# 6Ch_24Bit_FB_FeatherWing_RevB.net
KiCad netlist of a schematic drawn in EAGLE
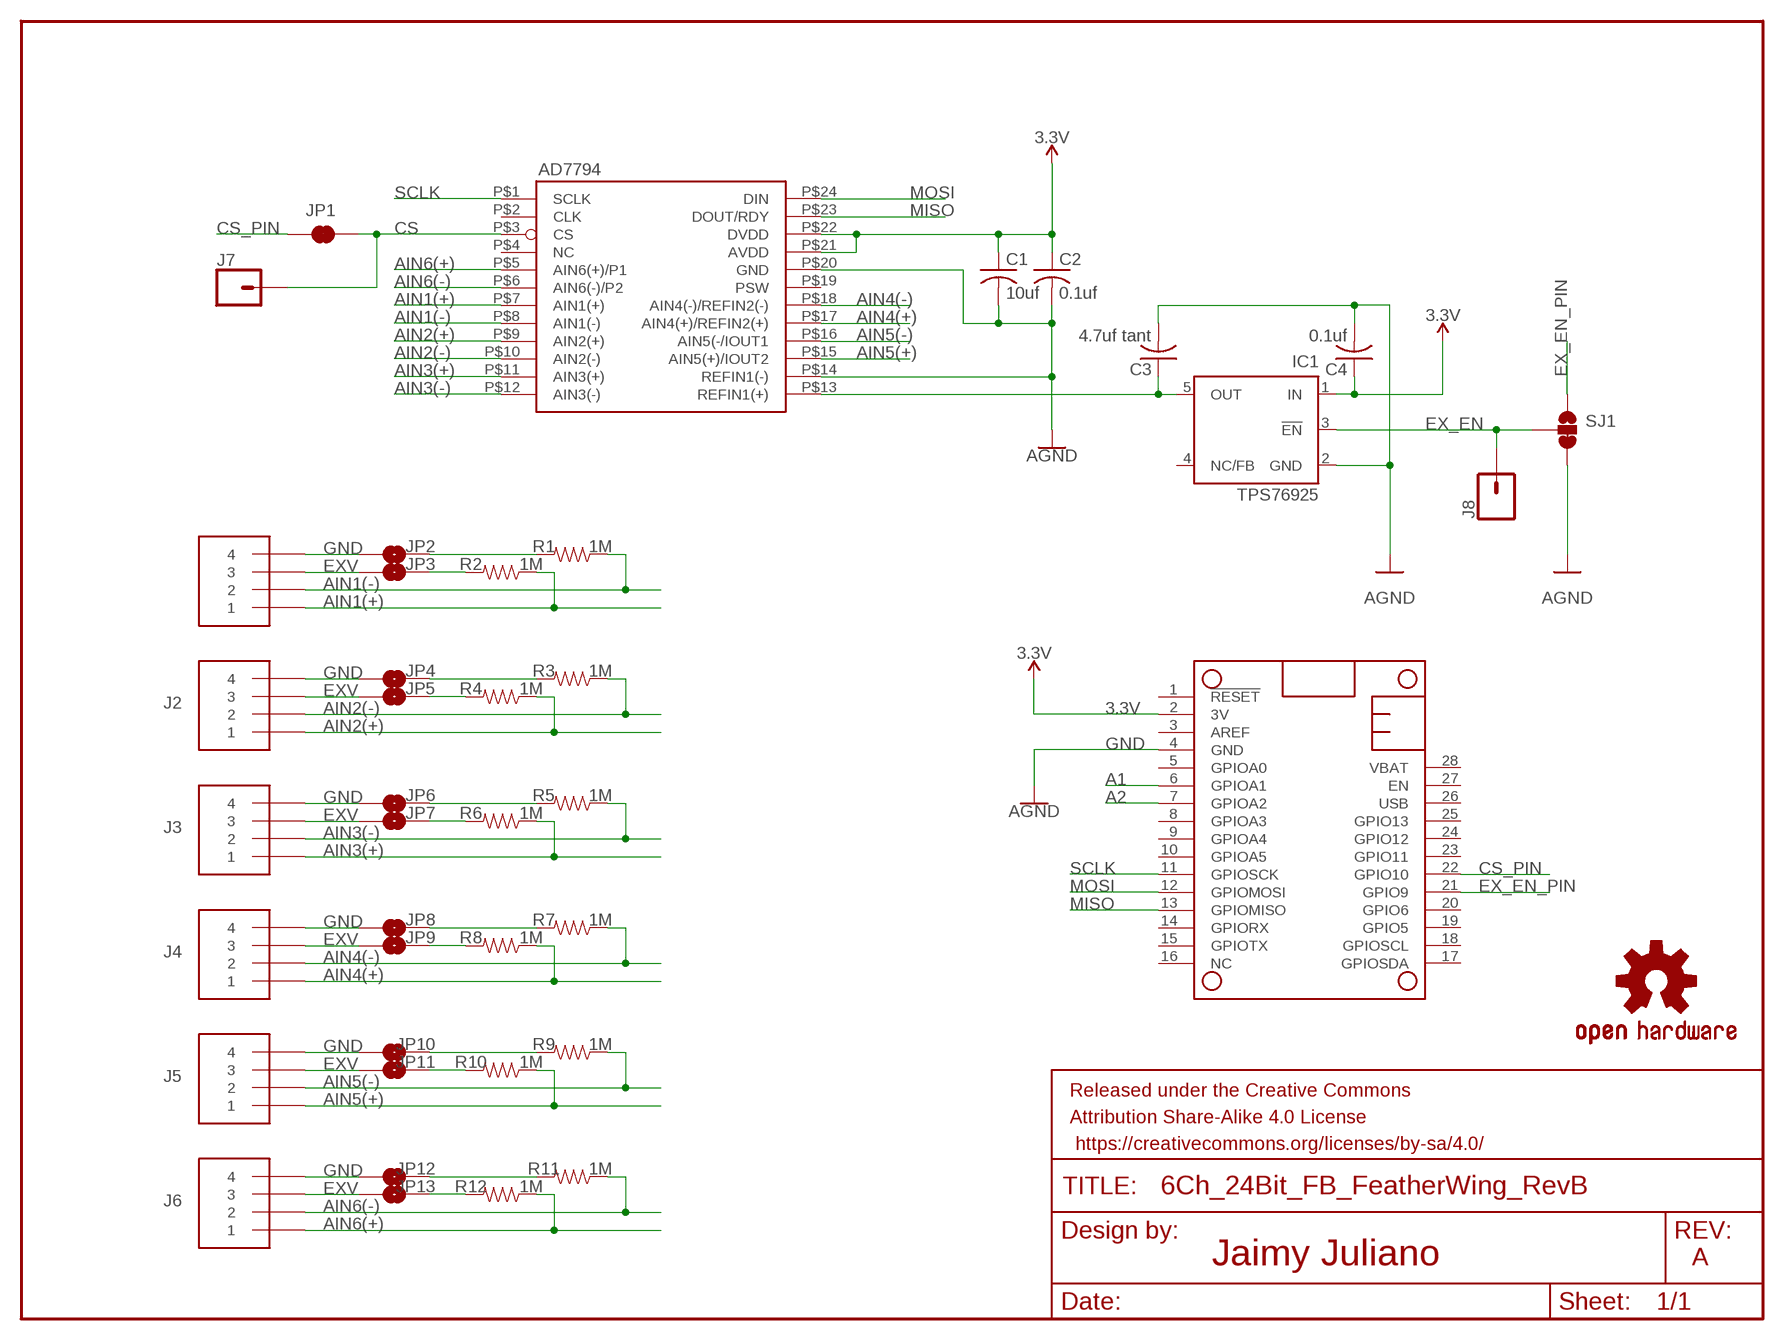
[diagram p0: schematic, sheet 1]

(export (version "E")
  (design (tool "Eeschema 10.0.6"))
  (components
    (comp (ref "C1")
      (value "10uf")
      (footprint "eagle-import:C0603")
      (libsource (lib "eagle-import") (part "C-USC0603"))
    )
    (comp (ref "C2")
      (value "0.1uf")
      (footprint "eagle-import:C0603")
      (libsource (lib "eagle-import") (part "C-USC0603"))
    )
    (comp (ref "C3")
      (value "4.7uf tant")
      (footprint "eagle-import:C1206K")
      (libsource (lib "eagle-import") (part "C-USC1206K"))
    )
    (comp (ref "C4")
      (value "0.1uf")
      (footprint "eagle-import:C0603")
      (libsource (lib "eagle-import") (part "C-USC0603"))
    )
    (comp (ref "FRAME2")
      (value "FRAME-LETTER")
      (footprint "eagle-import:CREATIVE_COMMONS")
      (libsource (lib "eagle-import") (part "FRAME-LETTER"))
    )
    (comp (ref "IC1")
      (value "TPS76925")
      (footprint "eagle-import:SOT23-DBV")
      (libsource (lib "eagle-import") (part "TPS77025"))
    )
    (comp (ref "J1")
      (value "CON_PTSM_SOCKET-4-PTH-VERT")
      (footprint "eagle-import:CON_PTSM_SOCKET-4-PTH-VERT")
      (libsource (lib "eagle-import") (part "CON_PTSM_SOCKET-4-PTH-VERT"))
    )
    (comp (ref "J2")
      (value "CON_PTSM_SOCKET-4-PTH-VERT")
      (footprint "eagle-import:CON_PTSM_SOCKET-4-PTH-VERT")
      (libsource (lib "eagle-import") (part "CON_PTSM_SOCKET-4-PTH-VERT"))
    )
    (comp (ref "J3")
      (value "CON_PTSM_SOCKET-4-PTH-VERT")
      (footprint "eagle-import:CON_PTSM_SOCKET-4-PTH-VERT")
      (libsource (lib "eagle-import") (part "CON_PTSM_SOCKET-4-PTH-VERT"))
    )
    (comp (ref "J4")
      (value "CON_PTSM_SOCKET-4-PTH-VERT")
      (footprint "eagle-import:CON_PTSM_SOCKET-4-PTH-VERT")
      (libsource (lib "eagle-import") (part "CON_PTSM_SOCKET-4-PTH-VERT"))
    )
    (comp (ref "J5")
      (value "CON_PTSM_SOCKET-4-PTH-VERT")
      (footprint "eagle-import:CON_PTSM_SOCKET-4-PTH-VERT")
      (libsource (lib "eagle-import") (part "CON_PTSM_SOCKET-4-PTH-VERT"))
    )
    (comp (ref "J6")
      (value "CON_PTSM_SOCKET-4-PTH-VERT")
      (footprint "eagle-import:CON_PTSM_SOCKET-4-PTH-VERT")
      (libsource (lib "eagle-import") (part "CON_PTSM_SOCKET-4-PTH-VERT"))
    )
    (comp (ref "J7")
      (value "CONN_01PTH_NO_SILK_YES_STOP")
      (footprint "eagle-import:1X01_NO_SILK")
      (libsource (lib "eagle-import") (part "CONN_01PTH_NO_SILK_YES_STOP"))
    )
    (comp (ref "J8")
      (value "CONN_01PTH_NO_SILK_YES_STOP")
      (footprint "eagle-import:1X01_NO_SILK")
      (libsource (lib "eagle-import") (part "CONN_01PTH_NO_SILK_YES_STOP"))
    )
    (comp (ref "JP1")
      (value "JUMPER-SMT_2_NC_TRACE_NO-SILK")
      (footprint "eagle-import:SMT-JUMPER_2_NC_TRACE_NO-SILK")
      (libsource (lib "eagle-import") (part "JUMPER-SMT_2_NC_TRACE_NO-SILK"))
    )
    (comp (ref "JP2")
      (value "JUMPER-SMT_2_NO_SILK")
      (footprint "eagle-import:SMT-JUMPER_2_NO_SILK")
      (libsource (lib "eagle-import") (part "JUMPER-SMT_2_NO_SILK"))
    )
    (comp (ref "JP3")
      (value "JUMPER-SMT_2_NO_SILK")
      (footprint "eagle-import:SMT-JUMPER_2_NO_SILK")
      (libsource (lib "eagle-import") (part "JUMPER-SMT_2_NO_SILK"))
    )
    (comp (ref "JP4")
      (value "JUMPER-SMT_2_NO_SILK")
      (footprint "eagle-import:SMT-JUMPER_2_NO_SILK")
      (libsource (lib "eagle-import") (part "JUMPER-SMT_2_NO_SILK"))
    )
    (comp (ref "JP5")
      (value "JUMPER-SMT_2_NO_SILK")
      (footprint "eagle-import:SMT-JUMPER_2_NO_SILK")
      (libsource (lib "eagle-import") (part "JUMPER-SMT_2_NO_SILK"))
    )
    (comp (ref "JP6")
      (value "JUMPER-SMT_2_NO_SILK")
      (footprint "eagle-import:SMT-JUMPER_2_NO_SILK")
      (libsource (lib "eagle-import") (part "JUMPER-SMT_2_NO_SILK"))
    )
    (comp (ref "JP7")
      (value "JUMPER-SMT_2_NO_SILK")
      (footprint "eagle-import:SMT-JUMPER_2_NO_SILK")
      (libsource (lib "eagle-import") (part "JUMPER-SMT_2_NO_SILK"))
    )
    (comp (ref "JP8")
      (value "JUMPER-SMT_2_NO_SILK")
      (footprint "eagle-import:SMT-JUMPER_2_NO_SILK")
      (libsource (lib "eagle-import") (part "JUMPER-SMT_2_NO_SILK"))
    )
    (comp (ref "JP9")
      (value "JUMPER-SMT_2_NO_SILK")
      (footprint "eagle-import:SMT-JUMPER_2_NO_SILK")
      (libsource (lib "eagle-import") (part "JUMPER-SMT_2_NO_SILK"))
    )
    (comp (ref "JP10")
      (value "JUMPER-SMT_2_NO_SILK")
      (footprint "eagle-import:SMT-JUMPER_2_NO_SILK")
      (libsource (lib "eagle-import") (part "JUMPER-SMT_2_NO_SILK"))
    )
    (comp (ref "JP11")
      (value "JUMPER-SMT_2_NO_SILK")
      (footprint "eagle-import:SMT-JUMPER_2_NO_SILK")
      (libsource (lib "eagle-import") (part "JUMPER-SMT_2_NO_SILK"))
    )
    (comp (ref "JP12")
      (value "JUMPER-SMT_2_NO_SILK")
      (footprint "eagle-import:SMT-JUMPER_2_NO_SILK")
      (libsource (lib "eagle-import") (part "JUMPER-SMT_2_NO_SILK"))
    )
    (comp (ref "JP13")
      (value "JUMPER-SMT_2_NO_SILK")
      (footprint "eagle-import:SMT-JUMPER_2_NO_SILK")
      (libsource (lib "eagle-import") (part "JUMPER-SMT_2_NO_SILK"))
    )
    (comp (ref "LOGO1")
      (value "OSHW-LOGOS")
      (footprint "eagle-import:OSHW-LOGO-S")
      (libsource (lib "eagle-import") (part "OSHW-LOGOS"))
    )
    (comp (ref "MS1")
      (value "FEATHERWING_NODIM")
      (footprint "eagle-import:FEATHERWING_DIM")
      (libsource (lib "eagle-import") (part "FEATHERWING_NODIM"))
    )
    (comp (ref "R1")
      (value "1M")
      (footprint "eagle-import:0603")
      (libsource (lib "eagle-import") (part "1MOHM-0603-1/4W-5%"))
    )
    (comp (ref "R2")
      (value "1M")
      (footprint "eagle-import:0603")
      (libsource (lib "eagle-import") (part "1MOHM-0603-1/4W-5%"))
    )
    (comp (ref "R3")
      (value "1M")
      (footprint "eagle-import:0603")
      (libsource (lib "eagle-import") (part "1MOHM-0603-1/4W-5%"))
    )
    (comp (ref "R4")
      (value "1M")
      (footprint "eagle-import:0603")
      (libsource (lib "eagle-import") (part "1MOHM-0603-1/4W-5%"))
    )
    (comp (ref "R5")
      (value "1M")
      (footprint "eagle-import:0603")
      (libsource (lib "eagle-import") (part "1MOHM-0603-1/4W-5%"))
    )
    (comp (ref "R6")
      (value "1M")
      (footprint "eagle-import:0603")
      (libsource (lib "eagle-import") (part "1MOHM-0603-1/4W-5%"))
    )
    (comp (ref "R7")
      (value "1M")
      (footprint "eagle-import:0603")
      (libsource (lib "eagle-import") (part "1MOHM-0603-1/4W-5%"))
    )
    (comp (ref "R8")
      (value "1M")
      (footprint "eagle-import:0603")
      (libsource (lib "eagle-import") (part "1MOHM-0603-1/4W-5%"))
    )
    (comp (ref "R9")
      (value "1M")
      (footprint "eagle-import:0603")
      (libsource (lib "eagle-import") (part "1MOHM-0603-1/4W-5%"))
    )
    (comp (ref "R10")
      (value "1M")
      (footprint "eagle-import:0603")
      (libsource (lib "eagle-import") (part "1MOHM-0603-1/4W-5%"))
    )
    (comp (ref "R11")
      (value "1M")
      (footprint "eagle-import:0603")
      (libsource (lib "eagle-import") (part "1MOHM-0603-1/4W-5%"))
    )
    (comp (ref "R12")
      (value "1M")
      (footprint "eagle-import:0603")
      (libsource (lib "eagle-import") (part "1MOHM-0603-1/4W-5%"))
    )
    (comp (ref "SJ1")
      (value "JUMPER-SMT_3_1-NC_TRACE_NO-SILK")
      (footprint "eagle-import:SMT-JUMPER_3_1-NC_TRACE_NO-SILK")
      (libsource (lib "eagle-import") (part "JUMPER-SMT_3_1-NC_TRACE_NO-SILK"))
    )
    (comp (ref "U1")
      (value "AD7794")
      (footprint "eagle-import:TSSOP-24")
      (libsource (lib "eagle-import") (part "AD7794"))
    )
  )
  (nets
    (net (code "1") (name "/A1") (class "Default")
      (node (ref "MS1") (pin "6") (pinfunction "GPIOA1_6") (pintype "bidirectional"))
    )
    (net (code "2") (name "/A2") (class "Default")
      (node (ref "MS1") (pin "7") (pinfunction "GPIOA2_7") (pintype "bidirectional"))
    )
    (net (code "3") (name "/AIN1(+)") (class "Default")
      (node (ref "J1") (pin "P$1") (pinfunction "1_P$1") (pintype "bidirectional"))
      (node (ref "R2") (pin "1") (pinfunction "1_1") (pintype "passive"))
      (node (ref "U1") (pin "P$7") (pinfunction "AIN1(+)_P$7") (pintype "bidirectional"))
    )
    (net (code "4") (name "/AIN1(-)") (class "Default")
      (node (ref "J1") (pin "P$2") (pinfunction "2_P$2") (pintype "bidirectional"))
      (node (ref "R1") (pin "1") (pinfunction "1_1") (pintype "passive"))
      (node (ref "U1") (pin "P$8") (pinfunction "AIN1(-)_P$8") (pintype "bidirectional"))
    )
    (net (code "5") (name "/AIN2(+)") (class "Default")
      (node (ref "J2") (pin "P$1") (pinfunction "1_P$1") (pintype "bidirectional"))
      (node (ref "R4") (pin "1") (pinfunction "1_1") (pintype "passive"))
      (node (ref "U1") (pin "P$9") (pinfunction "AIN2(+)_P$9") (pintype "bidirectional"))
    )
    (net (code "6") (name "/AIN2(-)") (class "Default")
      (node (ref "J2") (pin "P$2") (pinfunction "2_P$2") (pintype "bidirectional"))
      (node (ref "R3") (pin "1") (pinfunction "1_1") (pintype "passive"))
      (node (ref "U1") (pin "P$10") (pinfunction "AIN2(-)_P$10") (pintype "bidirectional"))
    )
    (net (code "7") (name "/AIN3(+)") (class "Default")
      (node (ref "J3") (pin "P$1") (pinfunction "1_P$1") (pintype "bidirectional"))
      (node (ref "R6") (pin "1") (pinfunction "1_1") (pintype "passive"))
      (node (ref "U1") (pin "P$11") (pinfunction "AIN3(+)_P$11") (pintype "bidirectional"))
    )
    (net (code "8") (name "/AIN3(-)") (class "Default")
      (node (ref "J3") (pin "P$2") (pinfunction "2_P$2") (pintype "bidirectional"))
      (node (ref "R5") (pin "1") (pinfunction "1_1") (pintype "passive"))
      (node (ref "U1") (pin "P$12") (pinfunction "AIN3(-)_P$12") (pintype "bidirectional"))
    )
    (net (code "9") (name "/AIN4(+)") (class "Default")
      (node (ref "J4") (pin "P$1") (pinfunction "1_P$1") (pintype "bidirectional"))
      (node (ref "R8") (pin "1") (pinfunction "1_1") (pintype "passive"))
      (node (ref "U1") (pin "P$17") (pinfunction "AIN4(+)/REFIN2(+)_P$17") (pintype "bidirectional"))
    )
    (net (code "10") (name "/AIN4(-)") (class "Default")
      (node (ref "J4") (pin "P$2") (pinfunction "2_P$2") (pintype "bidirectional"))
      (node (ref "R7") (pin "1") (pinfunction "1_1") (pintype "passive"))
      (node (ref "U1") (pin "P$18") (pinfunction "AIN4(-)/REFIN2(-)_P$18") (pintype "bidirectional"))
    )
    (net (code "11") (name "/AIN5(+)") (class "Default")
      (node (ref "J5") (pin "P$1") (pinfunction "1_P$1") (pintype "bidirectional"))
      (node (ref "R10") (pin "1") (pinfunction "1_1") (pintype "passive"))
      (node (ref "U1") (pin "P$15") (pinfunction "AIN5(+)/IOUT2_P$15") (pintype "bidirectional"))
    )
    (net (code "12") (name "/AIN5(-)") (class "Default")
      (node (ref "J5") (pin "P$2") (pinfunction "2_P$2") (pintype "bidirectional"))
      (node (ref "R9") (pin "1") (pinfunction "1_1") (pintype "passive"))
      (node (ref "U1") (pin "P$16") (pinfunction "AIN5(-/IOUT1_P$16") (pintype "bidirectional"))
    )
    (net (code "13") (name "/AIN6(+)") (class "Default")
      (node (ref "J6") (pin "P$1") (pinfunction "1_P$1") (pintype "bidirectional"))
      (node (ref "R12") (pin "1") (pinfunction "1_1") (pintype "passive"))
      (node (ref "U1") (pin "P$5") (pinfunction "AIN6(+)/P1_P$5") (pintype "bidirectional"))
    )
    (net (code "14") (name "/AIN6(-)") (class "Default")
      (node (ref "J6") (pin "P$2") (pinfunction "2_P$2") (pintype "bidirectional"))
      (node (ref "R11") (pin "1") (pinfunction "1_1") (pintype "passive"))
      (node (ref "U1") (pin "P$6") (pinfunction "AIN6(-)/P2_P$6") (pintype "bidirectional"))
    )
    (net (code "15") (name "/CS") (class "Default")
      (node (ref "J7") (pin "1") (pinfunction "1_1") (pintype "passive"))
      (node (ref "JP1") (pin "2") (pinfunction "2_2") (pintype "passive"))
      (node (ref "U1") (pin "P$3") (pinfunction "CS_P$3") (pintype "bidirectional"))
    )
    (net (code "16") (name "/CS_PIN") (class "Default")
      (node (ref "JP1") (pin "1") (pinfunction "1_1") (pintype "passive"))
      (node (ref "MS1") (pin "22") (pinfunction "GPIO10_22") (pintype "bidirectional"))
    )
    (net (code "17") (name "/EXV") (class "Default")
      (node (ref "C3") (pin "1") (pinfunction "1_1") (pintype "passive"))
      (node (ref "IC1") (pin "5") (pinfunction "OUT_5") (pintype "passive"))
      (node (ref "J1") (pin "P$3") (pinfunction "3_P$3") (pintype "bidirectional"))
      (node (ref "J2") (pin "P$3") (pinfunction "3_P$3") (pintype "bidirectional"))
      (node (ref "J3") (pin "P$3") (pinfunction "3_P$3") (pintype "bidirectional"))
      (node (ref "J4") (pin "P$3") (pinfunction "3_P$3") (pintype "bidirectional"))
      (node (ref "J5") (pin "P$3") (pinfunction "3_P$3") (pintype "bidirectional"))
      (node (ref "J6") (pin "P$3") (pinfunction "3_P$3") (pintype "bidirectional"))
      (node (ref "JP11") (pin "2") (pinfunction "2_2") (pintype "passive"))
      (node (ref "JP13") (pin "2") (pinfunction "2_2") (pintype "passive"))
      (node (ref "JP3") (pin "2") (pinfunction "2_2") (pintype "passive"))
      (node (ref "JP5") (pin "2") (pinfunction "2_2") (pintype "passive"))
      (node (ref "JP7") (pin "2") (pinfunction "2_2") (pintype "passive"))
      (node (ref "JP9") (pin "2") (pinfunction "2_2") (pintype "passive"))
      (node (ref "U1") (pin "P$13") (pinfunction "REFIN1(+)_P$13") (pintype "bidirectional"))
    )
    (net (code "18") (name "/EX_EN") (class "Default")
      (node (ref "IC1") (pin "3") (pinfunction "~{EN}_3") (pintype "input"))
      (node (ref "J8") (pin "1") (pinfunction "1_1") (pintype "passive"))
      (node (ref "SJ1") (pin "2") (pinfunction "2_2") (pintype "passive"))
    )
    (net (code "19") (name "/EX_EN_PIN") (class "Default")
      (node (ref "MS1") (pin "21") (pinfunction "GPIO9_21") (pintype "bidirectional"))
      (node (ref "SJ1") (pin "1") (pinfunction "1_1") (pintype "passive"))
    )
    (net (code "20") (name "/MISO") (class "Default")
      (node (ref "MS1") (pin "13") (pinfunction "GPIOMISO_13") (pintype "bidirectional"))
      (node (ref "U1") (pin "P$23") (pinfunction "DOUT/RDY_P$23") (pintype "bidirectional"))
    )
    (net (code "21") (name "/MOSI") (class "Default")
      (node (ref "MS1") (pin "12") (pinfunction "GPIOMOSI_12") (pintype "bidirectional"))
      (node (ref "U1") (pin "P$24") (pinfunction "DIN_P$24") (pintype "bidirectional"))
    )
    (net (code "22") (name "/SCLK") (class "Default")
      (node (ref "MS1") (pin "11") (pinfunction "GPIOSCK_11") (pintype "bidirectional"))
      (node (ref "U1") (pin "P$1") (pinfunction "SCLK_P$1") (pintype "bidirectional"))
    )
    (net (code "23") (name "/USB") (class "Default")
      (node (ref "MS1") (pin "26") (pinfunction "USB_26") (pintype "power_in"))
    )
    (net (code "24") (name "/VBAT") (class "Default")
      (node (ref "MS1") (pin "28") (pinfunction "VBAT_28") (pintype "power_in"))
    )
    (net (code "25") (name "3.3V") (class "Default")
      (node (ref "C1") (pin "1") (pinfunction "1_1") (pintype "passive"))
      (node (ref "C2") (pin "1") (pinfunction "1_1") (pintype "passive"))
      (node (ref "C4") (pin "1") (pinfunction "1_1") (pintype "passive"))
      (node (ref "IC1") (pin "1") (pinfunction "IN_1") (pintype "input"))
      (node (ref "MS1") (pin "2") (pinfunction "3V_2") (pintype "power_in"))
      (node (ref "U1") (pin "P$21") (pinfunction "AVDD_P$21") (pintype "bidirectional"))
      (node (ref "U1") (pin "P$22") (pinfunction "DVDD_P$22") (pintype "bidirectional"))
    )
    (net (code "26") (name "AGND") (class "Default")
      (node (ref "C1") (pin "2") (pinfunction "2_2") (pintype "passive"))
      (node (ref "C2") (pin "2") (pinfunction "2_2") (pintype "passive"))
      (node (ref "C3") (pin "2") (pinfunction "2_2") (pintype "passive"))
      (node (ref "C4") (pin "2") (pinfunction "2_2") (pintype "passive"))
      (node (ref "IC1") (pin "2") (pinfunction "GND_2") (pintype "power_in"))
      (node (ref "J1") (pin "P$4") (pinfunction "4_P$4") (pintype "bidirectional"))
      (node (ref "J2") (pin "P$4") (pinfunction "4_P$4") (pintype "bidirectional"))
      (node (ref "J3") (pin "P$4") (pinfunction "4_P$4") (pintype "bidirectional"))
      (node (ref "J4") (pin "P$4") (pinfunction "4_P$4") (pintype "bidirectional"))
      (node (ref "J5") (pin "P$4") (pinfunction "4_P$4") (pintype "bidirectional"))
      (node (ref "J6") (pin "P$4") (pinfunction "4_P$4") (pintype "bidirectional"))
      (node (ref "JP10") (pin "2") (pinfunction "2_2") (pintype "passive"))
      (node (ref "JP12") (pin "2") (pinfunction "2_2") (pintype "passive"))
      (node (ref "JP2") (pin "2") (pinfunction "2_2") (pintype "passive"))
      (node (ref "JP4") (pin "2") (pinfunction "2_2") (pintype "passive"))
      (node (ref "JP6") (pin "2") (pinfunction "2_2") (pintype "passive"))
      (node (ref "JP8") (pin "2") (pinfunction "2_2") (pintype "passive"))
      (node (ref "MS1") (pin "4") (pinfunction "GND_4") (pintype "power_in"))
      (node (ref "SJ1") (pin "3") (pinfunction "3_3") (pintype "passive"))
      (node (ref "U1") (pin "P$14") (pinfunction "REFIN1(-)_P$14") (pintype "bidirectional"))
      (node (ref "U1") (pin "P$20") (pinfunction "GND_P$20") (pintype "bidirectional"))
    )
    (net (code "27") (name "Net-(JP2-Pad1)") (class "Default")
      (node (ref "JP2") (pin "1") (pinfunction "1_1") (pintype "passive"))
      (node (ref "R1") (pin "2") (pinfunction "2_2") (pintype "passive"))
    )
    (net (code "28") (name "Net-(JP3-Pad1)") (class "Default")
      (node (ref "JP3") (pin "1") (pinfunction "1_1") (pintype "passive"))
      (node (ref "R2") (pin "2") (pinfunction "2_2") (pintype "passive"))
    )
    (net (code "29") (name "Net-(JP4-Pad1)") (class "Default")
      (node (ref "JP4") (pin "1") (pinfunction "1_1") (pintype "passive"))
      (node (ref "R3") (pin "2") (pinfunction "2_2") (pintype "passive"))
    )
    (net (code "30") (name "Net-(JP5-Pad1)") (class "Default")
      (node (ref "JP5") (pin "1") (pinfunction "1_1") (pintype "passive"))
      (node (ref "R4") (pin "2") (pinfunction "2_2") (pintype "passive"))
    )
    (net (code "31") (name "Net-(JP6-Pad1)") (class "Default")
      (node (ref "JP6") (pin "1") (pinfunction "1_1") (pintype "passive"))
      (node (ref "R5") (pin "2") (pinfunction "2_2") (pintype "passive"))
    )
    (net (code "32") (name "Net-(JP7-Pad1)") (class "Default")
      (node (ref "JP7") (pin "1") (pinfunction "1_1") (pintype "passive"))
      (node (ref "R6") (pin "2") (pinfunction "2_2") (pintype "passive"))
    )
    (net (code "33") (name "Net-(JP8-Pad1)") (class "Default")
      (node (ref "JP8") (pin "1") (pinfunction "1_1") (pintype "passive"))
      (node (ref "R7") (pin "2") (pinfunction "2_2") (pintype "passive"))
    )
    (net (code "34") (name "Net-(JP9-Pad1)") (class "Default")
      (node (ref "JP9") (pin "1") (pinfunction "1_1") (pintype "passive"))
      (node (ref "R8") (pin "2") (pinfunction "2_2") (pintype "passive"))
    )
    (net (code "35") (name "Net-(JP10-Pad1)") (class "Default")
      (node (ref "JP10") (pin "1") (pinfunction "1_1") (pintype "passive"))
      (node (ref "R9") (pin "2") (pinfunction "2_2") (pintype "passive"))
    )
    (net (code "36") (name "Net-(JP11-Pad1)") (class "Default")
      (node (ref "JP11") (pin "1") (pinfunction "1_1") (pintype "passive"))
      (node (ref "R10") (pin "2") (pinfunction "2_2") (pintype "passive"))
    )
    (net (code "37") (name "Net-(JP12-Pad1)") (class "Default")
      (node (ref "JP12") (pin "1") (pinfunction "1_1") (pintype "passive"))
      (node (ref "R11") (pin "2") (pinfunction "2_2") (pintype "passive"))
    )
    (net (code "38") (name "Net-(JP13-Pad1)") (class "Default")
      (node (ref "JP13") (pin "1") (pinfunction "1_1") (pintype "passive"))
      (node (ref "R12") (pin "2") (pinfunction "2_2") (pintype "passive"))
    )
    (net (code "39") (name "unconnected-(IC1-NC{slash}FB-Pad4)") (class "Default")
      (node (ref "IC1") (pin "4") (pinfunction "NC/FB_4") (pintype "passive"))
    )
    (net (code "40") (name "unconnected-(MS1-AREF-Pad3)") (class "Default")
      (node (ref "MS1") (pin "3") (pinfunction "AREF_3") (pintype "passive"))
    )
    (net (code "41") (name "unconnected-(MS1-EN-Pad27)") (class "Default")
      (node (ref "MS1") (pin "27") (pinfunction "EN_27") (pintype "passive"))
    )
    (net (code "42") (name "unconnected-(MS1-GPIO5-Pad19)") (class "Default")
      (node (ref "MS1") (pin "19") (pinfunction "GPIO5_19") (pintype "bidirectional"))
    )
    (net (code "43") (name "unconnected-(MS1-GPIO6-Pad20)") (class "Default")
      (node (ref "MS1") (pin "20") (pinfunction "GPIO6_20") (pintype "bidirectional"))
    )
    (net (code "44") (name "unconnected-(MS1-GPIO11-Pad23)") (class "Default")
      (node (ref "MS1") (pin "23") (pinfunction "GPIO11_23") (pintype "bidirectional"))
    )
    (net (code "45") (name "unconnected-(MS1-GPIO12-Pad24)") (class "Default")
      (node (ref "MS1") (pin "24") (pinfunction "GPIO12_24") (pintype "bidirectional"))
    )
    (net (code "46") (name "unconnected-(MS1-GPIO13-Pad25)") (class "Default")
      (node (ref "MS1") (pin "25") (pinfunction "GPIO13_25") (pintype "bidirectional"))
    )
    (net (code "47") (name "unconnected-(MS1-GPIOA0-Pad5)") (class "Default")
      (node (ref "MS1") (pin "5") (pinfunction "GPIOA0_5") (pintype "bidirectional"))
    )
    (net (code "48") (name "unconnected-(MS1-GPIOA3-Pad8)") (class "Default")
      (node (ref "MS1") (pin "8") (pinfunction "GPIOA3_8") (pintype "bidirectional"))
    )
    (net (code "49") (name "unconnected-(MS1-GPIOA4-Pad9)") (class "Default")
      (node (ref "MS1") (pin "9") (pinfunction "GPIOA4_9") (pintype "bidirectional"))
    )
    (net (code "50") (name "unconnected-(MS1-GPIOA5-Pad10)") (class "Default")
      (node (ref "MS1") (pin "10") (pinfunction "GPIOA5_10") (pintype "bidirectional"))
    )
    (net (code "51") (name "unconnected-(MS1-GPIORX-Pad14)") (class "Default")
      (node (ref "MS1") (pin "14") (pinfunction "GPIORX_14") (pintype "bidirectional"))
    )
    (net (code "52") (name "unconnected-(MS1-GPIOSCL-Pad18)") (class "Default")
      (node (ref "MS1") (pin "18") (pinfunction "GPIOSCL_18") (pintype "bidirectional"))
    )
    (net (code "53") (name "unconnected-(MS1-GPIOSDA-Pad17)") (class "Default")
      (node (ref "MS1") (pin "17") (pinfunction "GPIOSDA_17") (pintype "bidirectional"))
    )
    (net (code "54") (name "unconnected-(MS1-GPIOTX-Pad15)") (class "Default")
      (node (ref "MS1") (pin "15") (pinfunction "GPIOTX_15") (pintype "bidirectional"))
    )
    (net (code "55") (name "unconnected-(MS1-NC-Pad16)") (class "Default")
      (node (ref "MS1") (pin "16") (pinfunction "NC_16") (pintype "passive"))
    )
    (net (code "56") (name "unconnected-(MS1-~{RESET}-Pad1)") (class "Default")
      (node (ref "MS1") (pin "1") (pinfunction "~{RESET}_1") (pintype "input"))
    )
    (net (code "57") (name "unconnected-(U1-CLK-PadP$2)") (class "Default")
      (node (ref "U1") (pin "P$2") (pinfunction "CLK_P$2") (pintype "bidirectional"))
    )
    (net (code "58") (name "unconnected-(U1-NC-PadP$4)") (class "Default")
      (node (ref "U1") (pin "P$4") (pinfunction "NC_P$4") (pintype "bidirectional"))
    )
    (net (code "59") (name "unconnected-(U1-PSW-PadP$19)") (class "Default")
      (node (ref "U1") (pin "P$19") (pinfunction "PSW_P$19") (pintype "bidirectional"))
    )
  )
)
